# schematic.net
KiCad netlist of a schematic drawn in EasyEDA
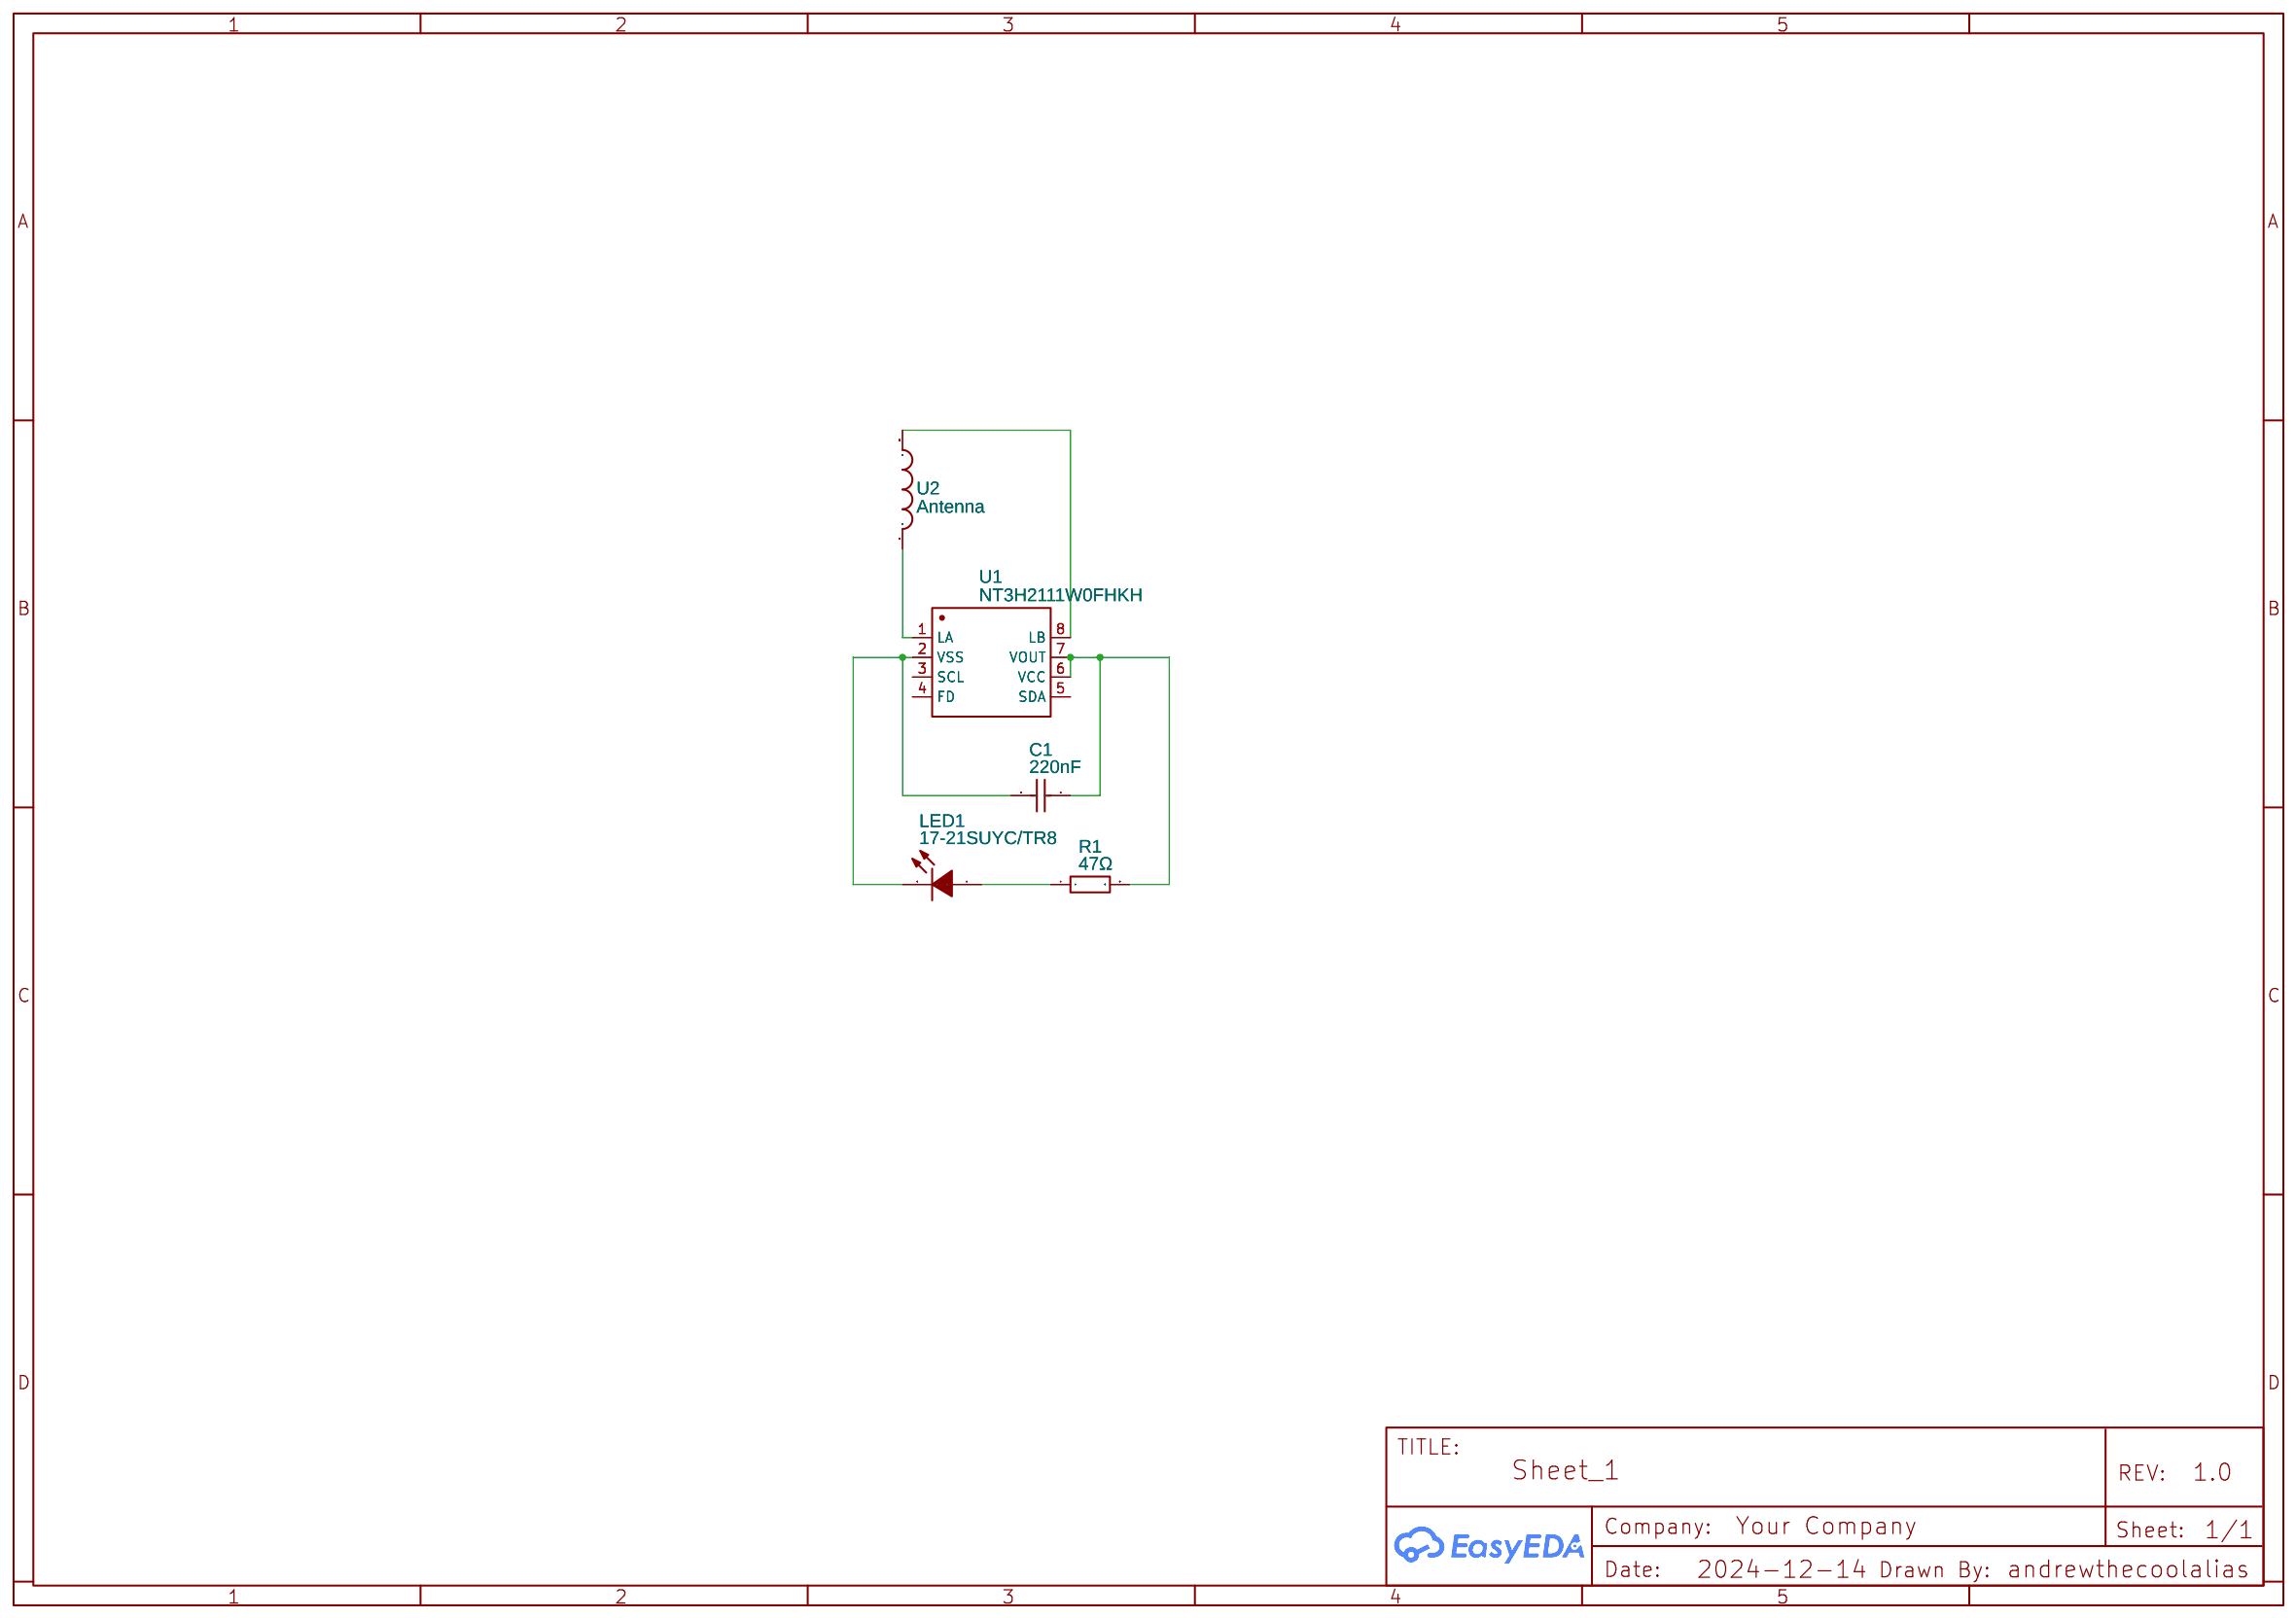
[diagram p0: schematic sheet]

(export (version "E")
  (design (tool "Eeschema 10.0.6"))
  (components
    (comp (ref "C1")
      (value "220nF")
      (fields
        (field (name "Manufacturer Part") "CL10B224KA8NNNC")
        (field (name "Manufacturer") "SAMSUNG(三星)")
      )
      (libsource (lib "") (part "CL10B224KA8NNNC"))
    )
    (comp (ref "LED1")
      (value "17-21SUYC/TR8")
      (fields (field (name "Manufacturer Part") "KT-0805黄灯") (field (name "Manufacturer") "KENTO"))
      (libsource (lib "") (part "17-21SUYC/TR8"))
    )
    (comp (ref "R1")
      (value "47Ω")
      (fields
        (field (name "Manufacturer Part") "0603WAF470JT5E")
        (field (name "Manufacturer") "UNI-ROYAL(厚声)")
      )
      (libsource (lib "") (part "0603WAF470JT5E"))
    )
    (comp (ref "U1")
      (value "NT3H2111W0FHKH")
      (fields (field (name "Manufacturer") "NXP(恩智浦)"))
      (libsource (lib "") (part "NT3H2111W0FHKH"))
    )
    (comp (ref "U2") (value "Antenna") (libsource (lib "") (part "Antenna")))
  )
  (nets
    (net (code "1") (name "Net-(LED1-+)") (class "Default")
      (node (ref "LED1") (pin "1") (pinfunction "+_1") (pintype "unspecified"))
      (node (ref "R1") (pin "1") (pinfunction "1_1") (pintype "input"))
    )
    (net (code "2") (name "Net-(LED1--)") (class "Default")
      (node (ref "C1") (pin "1") (pinfunction "1_1") (pintype "input"))
      (node (ref "LED1") (pin "2") (pinfunction "-_2") (pintype "unspecified"))
      (node (ref "U1") (pin "2") (pinfunction "VSS_2") (pintype "unspecified"))
    )
    (net (code "3") (name "Net-(U1-LA)") (class "Default")
      (node (ref "U1") (pin "1") (pinfunction "LA_1") (pintype "unspecified"))
      (node (ref "U2") (pin "P$1") (pinfunction "P$1_P$1") (pintype "unspecified"))
    )
    (net (code "4") (name "Net-(U1-LB)") (class "Default")
      (node (ref "U1") (pin "8") (pinfunction "LB_8") (pintype "unspecified"))
      (node (ref "U2") (pin "P$2") (pinfunction "P$2_P$2") (pintype "unspecified"))
    )
    (net (code "5") (name "Net-(U1-VCC)") (class "Default")
      (node (ref "C1") (pin "2") (pinfunction "2_2") (pintype "input"))
      (node (ref "R1") (pin "2") (pinfunction "2_2") (pintype "input"))
      (node (ref "U1") (pin "6") (pinfunction "VCC_6") (pintype "unspecified"))
      (node (ref "U1") (pin "7") (pinfunction "VOUT_7") (pintype "unspecified"))
    )
    (net (code "6") (name "unconnected-(U1-FD-Pad4)") (class "Default")
      (node (ref "U1") (pin "4") (pinfunction "FD_4") (pintype "unspecified"))
    )
    (net (code "7") (name "unconnected-(U1-SCL-Pad3)") (class "Default")
      (node (ref "U1") (pin "3") (pinfunction "SCL_3") (pintype "unspecified"))
    )
    (net (code "8") (name "unconnected-(U1-SDA-Pad5)") (class "Default")
      (node (ref "U1") (pin "5") (pinfunction "SDA_5") (pintype "unspecified"))
    )
  )
)
